# EnvMonitor.net
KiCad netlist of a schematic drawn in Altium Designer
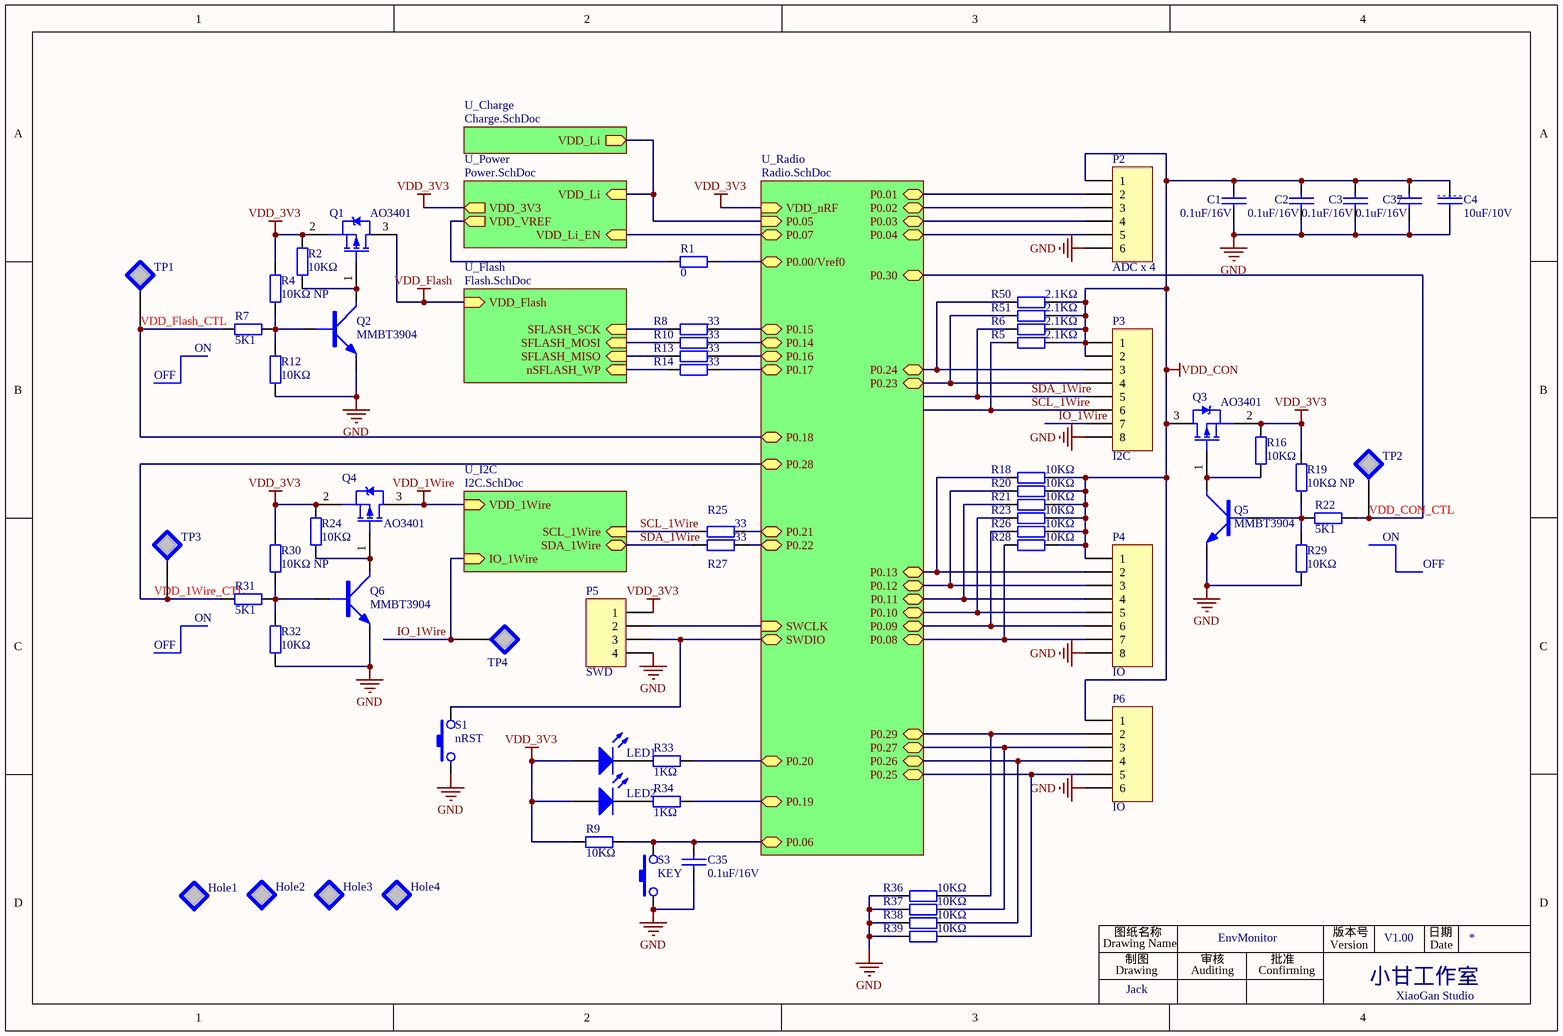
[diagram p0: EnvMonitor.SchDoc]

(export (version "E")
  (design (tool "Eeschema 10.0.6"))
  (components
    (comp (ref "C1")
      (value "0.1uF/16V")
      (footprint "0603R")
      (description "贴片陶瓷电容")
      (libsource (lib "") (part "CAP_1"))
    )
    (comp (ref "C2")
      (value "0.1uF/16V")
      (footprint "0603R")
      (description "贴片陶瓷电容")
      (libsource (lib "") (part "CAP_1"))
    )
    (comp (ref "C3")
      (value "0.1uF/16V")
      (footprint "0603R")
      (description "贴片陶瓷电容")
      (libsource (lib "") (part "CAP_1"))
    )
    (comp (ref "C4")
      (value "10uF/10V")
      (footprint "0805R")
      (description "贴片陶瓷电容")
      (fields (field (name "AUTHOR") "叶建峰"))
      (libsource (lib "*") (part "CAP"))
    )
    (comp (ref "C35")
      (value "0.1uF/16V")
      (footprint "0603R")
      (description "贴片陶瓷电容")
      (libsource (lib "") (part "CAP_1"))
    )
    (comp (ref "C37")
      (value "0.1uF/16V")
      (footprint "0603R")
      (description "贴片陶瓷电容")
      (libsource (lib "") (part "CAP_1"))
    )
    (comp (ref "Hole1")
      (value "~")
      (footprint "HOLE-3.2")
      (description "Test Point")
      (fields (field (name "AUTHOR") "叶建峰"))
      (libsource (lib "") (part "TESTPOINT_1"))
    )
    (comp (ref "Hole2")
      (value "~")
      (footprint "HOLE-3.2")
      (description "Test Point")
      (fields (field (name "AUTHOR") "叶建峰"))
      (libsource (lib "") (part "TESTPOINT_1"))
    )
    (comp (ref "Hole3")
      (value "~")
      (footprint "HOLE-3.2")
      (description "Test Point")
      (fields (field (name "AUTHOR") "叶建峰"))
      (libsource (lib "") (part "TESTPOINT_1"))
    )
    (comp (ref "Hole4")
      (value "~")
      (footprint "HOLE-3.2")
      (description "Test Point")
      (fields (field (name "AUTHOR") "叶建峰"))
      (libsource (lib "") (part "TESTPOINT_1"))
    )
    (comp (ref "LED1")
      (value "LED_0603")
      (footprint "LED-0603")
      (description "LED_0603 Typical RED, GREEN, YELLOW, AMBER GaAs LED")
      (libsource (lib "altium-import") (part "root_0_LED_0603_"))
    )
    (comp (ref "LED2")
      (value "LED_0603")
      (footprint "LED-0603")
      (description "LED_0603 Typical RED, GREEN, YELLOW, AMBER GaAs LED")
      (libsource (lib "altium-import") (part "root_0_LED_0603_"))
    )
    (comp (ref "P2")
      (value "ADC x 4")
      (footprint "CON6-2.0")
      (description "Header, 6-Pin")
      (fields (field (name "PUBLISHER") "Altium Limited"))
      (libsource (lib "Miscellaneous Connectors") (part "Header 6"))
    )
    (comp (ref "P3")
      (value "I2C")
      (footprint "CON8-2.0")
      (description "Header, 8-Pin")
      (fields (field (name "PUBLISHER") "Altium Limited"))
      (libsource (lib "Miscellaneous Connectors") (part "Header 8"))
    )
    (comp (ref "P4")
      (value "IO")
      (footprint "CON8-2.0")
      (description "Header, 8-Pin")
      (fields (field (name "PUBLISHER") "Altium Limited"))
      (libsource (lib "Miscellaneous Connectors") (part "Header 8"))
    )
    (comp (ref "P5")
      (value "SWD")
      (footprint "CON4-2.0")
      (description "Header, 4-Pin")
      (fields (field (name "PUBLISHER") "Altium Limited"))
      (libsource (lib "Miscellaneous Connectors") (part "Header 4"))
    )
    (comp (ref "P6")
      (value "IO")
      (footprint "CON6-2.0")
      (description "Header, 6-Pin")
      (fields (field (name "PUBLISHER") "Altium Limited"))
      (libsource (lib "Miscellaneous Connectors") (part "Header 6"))
    )
    (comp (ref "Q1")
      (value "AO3401")
      (footprint "SOT-23")
      (description "-30V,-3.8A   PMOS  70-120mΩ")
      (fields (field (name "MANUFACTURER") "DIODES"))
      (libsource (lib "led") (part "DMP3098L"))
    )
    (comp (ref "Q2")
      (value "MMBT3904")
      (footprint "SOT-23")
      (description "NPN三极管")
      (libsource (lib "*") (part "9013"))
    )
    (comp (ref "Q3")
      (value "AO3401")
      (footprint "SOT-23")
      (description "-30V,-3.8A   PMOS  70-120mΩ")
      (fields (field (name "MANUFACTURER") "DIODES"))
      (libsource (lib "led") (part "DMP3098L"))
    )
    (comp (ref "Q4")
      (value "AO3401")
      (footprint "SOT-23")
      (description "-30V,-3.8A   PMOS  70-120mΩ")
      (fields (field (name "MANUFACTURER") "DIODES"))
      (libsource (lib "led") (part "DMP3098L"))
    )
    (comp (ref "Q5")
      (value "MMBT3904")
      (footprint "SOT-23")
      (description "NPN三极管")
      (libsource (lib "*") (part "9013"))
    )
    (comp (ref "Q6")
      (value "MMBT3904")
      (footprint "SOT-23")
      (description "NPN三极管")
      (libsource (lib "*") (part "9013"))
    )
    (comp (ref "R1")
      (value "0")
      (footprint "0603R")
      (libsource (lib "altium-import") (part "root_2_RES_0603_"))
    )
    (comp (ref "R2")
      (value "10KΩ")
      (footprint "0603R")
      (libsource (lib "altium-import") (part "root_1_mirrored_RES_0603_"))
    )
    (comp (ref "R4")
      (value "10KΩ NP")
      (footprint "0603R")
      (libsource (lib "altium-import") (part "root_1_mirrored_RES_0603_"))
    )
    (comp (ref "R5")
      (value "2.1KΩ")
      (footprint "0603R")
      (libsource (lib "altium-import") (part "root_2_RES_0603_"))
    )
    (comp (ref "R6")
      (value "2.1KΩ")
      (footprint "0603R")
      (libsource (lib "altium-import") (part "root_2_RES_0603_"))
    )
    (comp (ref "R7")
      (value "5K1")
      (footprint "0603R")
      (libsource (lib "altium-import") (part "root_0_mirrored_RES_0603_"))
    )
    (comp (ref "R8")
      (value "33")
      (footprint "0603R")
      (libsource (lib "altium-import") (part "root_2_RES_0603_"))
    )
    (comp (ref "R9")
      (value "10KΩ")
      (footprint "0603R")
      (libsource (lib "altium-import") (part "root_2_RES_0603_"))
    )
    (comp (ref "R10")
      (value "33")
      (footprint "0603R")
      (libsource (lib "altium-import") (part "root_2_RES_0603_"))
    )
    (comp (ref "R12")
      (value "10KΩ")
      (footprint "0603R")
      (libsource (lib "altium-import") (part "root_1_mirrored_RES_0603_"))
    )
    (comp (ref "R13")
      (value "33")
      (footprint "0603R")
      (libsource (lib "altium-import") (part "root_2_RES_0603_"))
    )
    (comp (ref "R14")
      (value "33")
      (footprint "0603R")
      (libsource (lib "altium-import") (part "root_2_RES_0603_"))
    )
    (comp (ref "R16")
      (value "10KΩ")
      (footprint "0603R")
      (libsource (lib "altium-import") (part "root_1_RES_0603_"))
    )
    (comp (ref "R18")
      (value "10KΩ")
      (footprint "0603R")
      (libsource (lib "altium-import") (part "root_2_RES_0603_"))
    )
    (comp (ref "R19")
      (value "10KΩ NP")
      (footprint "0603R")
      (libsource (lib "altium-import") (part "root_1_RES_0603_"))
    )
    (comp (ref "R20")
      (value "10KΩ")
      (footprint "0603R")
      (libsource (lib "altium-import") (part "root_2_RES_0603_"))
    )
    (comp (ref "R21")
      (value "10KΩ")
      (footprint "0603R")
      (libsource (lib "altium-import") (part "root_2_RES_0603_"))
    )
    (comp (ref "R22")
      (value "5K1")
      (footprint "0603R")
      (libsource (lib "altium-import") (part "root_0_RES_0603_"))
    )
    (comp (ref "R23")
      (value "10KΩ")
      (footprint "0603R")
      (libsource (lib "altium-import") (part "root_2_RES_0603_"))
    )
    (comp (ref "R24")
      (value "10KΩ")
      (footprint "0603R")
      (libsource (lib "altium-import") (part "root_1_mirrored_RES_0603_"))
    )
    (comp (ref "R25")
      (value "33")
      (footprint "0603R")
      (libsource (lib "altium-import") (part "root_2_RES_0603_"))
    )
    (comp (ref "R26")
      (value "10KΩ")
      (footprint "0603R")
      (libsource (lib "altium-import") (part "root_2_RES_0603_"))
    )
    (comp (ref "R27")
      (value "33")
      (footprint "0603R")
      (libsource (lib "altium-import") (part "root_2_RES_0603_"))
    )
    (comp (ref "R28")
      (value "10KΩ")
      (footprint "0603R")
      (libsource (lib "altium-import") (part "root_2_RES_0603_"))
    )
    (comp (ref "R29")
      (value "10KΩ")
      (footprint "0603R")
      (libsource (lib "altium-import") (part "root_1_RES_0603_"))
    )
    (comp (ref "R30")
      (value "10KΩ NP")
      (footprint "0603R")
      (libsource (lib "altium-import") (part "root_1_mirrored_RES_0603_"))
    )
    (comp (ref "R31")
      (value "5K1")
      (footprint "0603R")
      (libsource (lib "altium-import") (part "root_0_mirrored_RES_0603_"))
    )
    (comp (ref "R32")
      (value "10KΩ")
      (footprint "0603R")
      (libsource (lib "altium-import") (part "root_1_mirrored_RES_0603_"))
    )
    (comp (ref "R33")
      (value "1KΩ")
      (footprint "0603R")
      (libsource (lib "altium-import") (part "root_2_RES_0603_"))
    )
    (comp (ref "R34")
      (value "1KΩ")
      (footprint "0603R")
      (libsource (lib "altium-import") (part "root_2_RES_0603_"))
    )
    (comp (ref "R36")
      (value "10KΩ")
      (footprint "0603R")
      (libsource (lib "altium-import") (part "root_2_RES_0603_"))
    )
    (comp (ref "R37")
      (value "10KΩ")
      (footprint "0603R")
      (libsource (lib "altium-import") (part "root_2_RES_0603_"))
    )
    (comp (ref "R38")
      (value "10KΩ")
      (footprint "0603R")
      (libsource (lib "altium-import") (part "root_2_RES_0603_"))
    )
    (comp (ref "R39")
      (value "10KΩ")
      (footprint "0603R")
      (libsource (lib "altium-import") (part "root_2_RES_0603_"))
    )
    (comp (ref "R50")
      (value "2.1KΩ")
      (footprint "0603R")
      (libsource (lib "altium-import") (part "root_2_mirrored_RES_0603_"))
    )
    (comp (ref "R51")
      (value "2.1KΩ")
      (footprint "0603R")
      (libsource (lib "altium-import") (part "root_2_mirrored_RES_0603_"))
    )
    (comp (ref "S1") (value "nRST") (footprint "KEY-6S") (libsource (lib "RC-sheet") (part "SW-PB")))
    (comp (ref "S3") (value "KEY") (footprint "KEY-6S") (libsource (lib "RC-sheet") (part "SW-PB")))
    (comp (ref "TP1")
      (value "~")
      (footprint "MARKER-C")
      (description "Test Point")
      (fields (field (name "AUTHOR") "叶建峰"))
      (libsource (lib "*") (part "TESTPOINT"))
    )
    (comp (ref "TP2")
      (value "~")
      (footprint "MARKER-C")
      (description "Test Point")
      (fields (field (name "AUTHOR") "叶建峰"))
      (libsource (lib "*") (part "TESTPOINT"))
    )
    (comp (ref "TP3")
      (value "~")
      (footprint "MARKER-C")
      (description "Test Point")
      (fields (field (name "AUTHOR") "叶建峰"))
      (libsource (lib "*") (part "TESTPOINT"))
    )
    (comp (ref "TP4")
      (value "~")
      (footprint "MARKER-C")
      (description "Test Point")
      (fields (field (name "AUTHOR") "叶建峰"))
      (libsource (lib "*") (part "TESTPOINT"))
    )
  )
  (nets
    (net (code "1") (name "/IO_1Wire") (class "Default")
      (node (ref "P3") (pin "7") (pinfunction "7_7") (pintype "passive"))
      (node (ref "TP4") (pin "0") (pintype "passive"))
    )
    (net (code "2") (name "/P0.00{slash}Vref0") (class "Default")
      (node (ref "R1") (pin "1") (pinfunction "1_1") (pintype "passive"))
    )
    (net (code "3") (name "/P0.01") (class "Default")
      (node (ref "P2") (pin "2") (pinfunction "2_2") (pintype "passive"))
    )
    (net (code "4") (name "/P0.02") (class "Default")
      (node (ref "P2") (pin "3") (pinfunction "3_3") (pintype "passive"))
    )
    (net (code "5") (name "/P0.03") (class "Default")
      (node (ref "P2") (pin "4") (pinfunction "4_4") (pintype "passive"))
    )
    (net (code "6") (name "/P0.04") (class "Default")
      (node (ref "P2") (pin "5") (pinfunction "5_5") (pintype "passive"))
    )
    (net (code "7") (name "/P0.06") (class "Default")
      (node (ref "C35") (pin "2") (pinfunction "2_2") (pintype "passive"))
      (node (ref "R9") (pin "1") (pinfunction "1_1") (pintype "passive"))
      (node (ref "S3") (pin "2") (pinfunction "2_2") (pintype "passive"))
    )
    (net (code "9") (name "/P0.08") (class "Default")
      (node (ref "P4") (pin "7") (pinfunction "7_7") (pintype "passive"))
      (node (ref "R28") (pin "2") (pinfunction "2_2") (pintype "passive"))
    )
    (net (code "10") (name "/P0.09") (class "Default")
      (node (ref "P4") (pin "6") (pinfunction "6_6") (pintype "passive"))
      (node (ref "R26") (pin "2") (pinfunction "2_2") (pintype "passive"))
    )
    (net (code "11") (name "/P0.10") (class "Default")
      (node (ref "P4") (pin "5") (pinfunction "5_5") (pintype "passive"))
      (node (ref "R23") (pin "2") (pinfunction "2_2") (pintype "passive"))
    )
    (net (code "12") (name "/P0.11") (class "Default")
      (node (ref "P4") (pin "4") (pinfunction "4_4") (pintype "passive"))
      (node (ref "R21") (pin "2") (pinfunction "2_2") (pintype "passive"))
    )
    (net (code "13") (name "/P0.12") (class "Default")
      (node (ref "P4") (pin "3") (pinfunction "3_3") (pintype "passive"))
      (node (ref "R20") (pin "2") (pinfunction "2_2") (pintype "passive"))
    )
    (net (code "14") (name "/P0.13") (class "Default")
      (node (ref "P4") (pin "2") (pinfunction "2_2") (pintype "passive"))
      (node (ref "R18") (pin "2") (pinfunction "2_2") (pintype "passive"))
    )
    (net (code "15") (name "/P0.14") (class "Default")
      (node (ref "R10") (pin "1") (pinfunction "1_1") (pintype "passive"))
    )
    (net (code "16") (name "/P0.15") (class "Default")
      (node (ref "R8") (pin "1") (pinfunction "1_1") (pintype "passive"))
    )
    (net (code "17") (name "/P0.16") (class "Default")
      (node (ref "R13") (pin "1") (pinfunction "1_1") (pintype "passive"))
    )
    (net (code "18") (name "/P0.17") (class "Default")
      (node (ref "R14") (pin "1") (pinfunction "1_1") (pintype "passive"))
    )
    (net (code "19") (name "/P0.19") (class "Default")
      (node (ref "R34") (pin "1") (pinfunction "1_1") (pintype "passive"))
    )
    (net (code "20") (name "/P0.20") (class "Default")
      (node (ref "R33") (pin "1") (pinfunction "1_1") (pintype "passive"))
    )
    (net (code "21") (name "/P0.21") (class "Default")
      (node (ref "R25") (pin "1") (pinfunction "1_1") (pintype "passive"))
    )
    (net (code "22") (name "/P0.22") (class "Default")
      (node (ref "R27") (pin "1") (pinfunction "1_1") (pintype "passive"))
    )
    (net (code "23") (name "/P0.23") (class "Default")
      (node (ref "P3") (pin "4") (pinfunction "4_4") (pintype "passive"))
      (node (ref "R51") (pin "1") (pinfunction "1_1") (pintype "passive"))
    )
    (net (code "24") (name "/P0.24") (class "Default")
      (node (ref "P3") (pin "3") (pinfunction "3_3") (pintype "passive"))
      (node (ref "R50") (pin "1") (pinfunction "1_1") (pintype "passive"))
    )
    (net (code "25") (name "/P0.25") (class "Default")
      (node (ref "P6") (pin "5") (pinfunction "5_5") (pintype "passive"))
      (node (ref "R39") (pin "1") (pinfunction "1_1") (pintype "passive"))
    )
    (net (code "26") (name "/P0.26") (class "Default")
      (node (ref "P6") (pin "4") (pinfunction "4_4") (pintype "passive"))
      (node (ref "R38") (pin "1") (pinfunction "1_1") (pintype "passive"))
    )
    (net (code "27") (name "/P0.27") (class "Default")
      (node (ref "P6") (pin "3") (pinfunction "3_3") (pintype "passive"))
      (node (ref "R37") (pin "1") (pinfunction "1_1") (pintype "passive"))
    )
    (net (code "28") (name "/P0.29") (class "Default")
      (node (ref "P6") (pin "2") (pinfunction "2_2") (pintype "passive"))
      (node (ref "R36") (pin "1") (pinfunction "1_1") (pintype "passive"))
    )
    (net (code "29") (name "/SCL_1Wire") (class "Default")
      (node (ref "P3") (pin "6") (pinfunction "6_6") (pintype "passive"))
      (node (ref "R25") (pin "2") (pinfunction "2_2") (pintype "passive"))
      (node (ref "R5") (pin "2") (pinfunction "2_2") (pintype "passive"))
    )
    (net (code "30") (name "/SDA_1Wire") (class "Default")
      (node (ref "P3") (pin "5") (pinfunction "5_5") (pintype "passive"))
      (node (ref "R27") (pin "2") (pinfunction "2_2") (pintype "passive"))
      (node (ref "R6") (pin "2") (pinfunction "2_2") (pintype "passive"))
    )
    (net (code "31") (name "/SFLASH_MISO") (class "Default")
      (node (ref "R13") (pin "2") (pinfunction "2_2") (pintype "passive"))
    )
    (net (code "32") (name "/SFLASH_MOSI") (class "Default")
      (node (ref "R10") (pin "2") (pinfunction "2_2") (pintype "passive"))
    )
    (net (code "33") (name "/SFLASH_SCK") (class "Default")
      (node (ref "R8") (pin "2") (pinfunction "2_2") (pintype "passive"))
    )
    (net (code "34") (name "/SWCLK") (class "Default")
      (node (ref "P5") (pin "2") (pinfunction "2_2") (pintype "passive"))
    )
    (net (code "35") (name "/SWDIO") (class "Default")
      (node (ref "P5") (pin "3") (pinfunction "3_3") (pintype "passive"))
      (node (ref "S1") (pin "2") (pinfunction "2_2") (pintype "passive"))
    )
    (net (code "36") (name "/VDD_1Wire_CTL") (class "Default")
      (node (ref "R31") (pin "2") (pinfunction "2_2") (pintype "passive"))
      (node (ref "TP3") (pin "0") (pintype "passive"))
    )
    (net (code "37") (name "/VDD_CON_CTL") (class "Default")
      (node (ref "R22") (pin "2") (pinfunction "2_2") (pintype "passive"))
      (node (ref "TP2") (pin "0") (pintype "passive"))
    )
    (net (code "38") (name "/VDD_Flash_CTL") (class "Default")
      (node (ref "R7") (pin "2") (pinfunction "2_2") (pintype "passive"))
      (node (ref "TP1") (pin "0") (pintype "passive"))
    )
    (net (code "40") (name "/VDD_VREF") (class "Default")
      (node (ref "R1") (pin "2") (pinfunction "2_2") (pintype "passive"))
    )
    (net (code "41") (name "/nSFLASH_WP") (class "Default")
      (node (ref "R14") (pin "2") (pinfunction "2_2") (pintype "passive"))
    )
    (net (code "42") (name "GND") (class "Default")
      (node (ref "C1") (pin "2") (pinfunction "2_2") (pintype "passive"))
      (node (ref "C2") (pin "2") (pinfunction "2_2") (pintype "passive"))
      (node (ref "C3") (pin "2") (pinfunction "2_2") (pintype "passive"))
      (node (ref "C35") (pin "1") (pinfunction "1_1") (pintype "passive"))
      (node (ref "C37") (pin "2") (pinfunction "2_2") (pintype "passive"))
      (node (ref "C4") (pin "2") (pinfunction "2_2") (pintype "passive"))
      (node (ref "P2") (pin "6") (pinfunction "6_6") (pintype "passive"))
      (node (ref "P3") (pin "8") (pinfunction "8_8") (pintype "passive"))
      (node (ref "P4") (pin "8") (pinfunction "8_8") (pintype "passive"))
      (node (ref "P5") (pin "4") (pinfunction "4_4") (pintype "passive"))
      (node (ref "P6") (pin "6") (pinfunction "6_6") (pintype "passive"))
      (node (ref "Q2") (pin "2") (pintype "passive"))
      (node (ref "Q5") (pin "2") (pintype "passive"))
      (node (ref "Q6") (pin "2") (pintype "passive"))
      (node (ref "R12") (pin "1") (pinfunction "1_1") (pintype "passive"))
      (node (ref "R29") (pin "1") (pinfunction "1_1") (pintype "passive"))
      (node (ref "R32") (pin "1") (pinfunction "1_1") (pintype "passive"))
      (node (ref "R36") (pin "2") (pinfunction "2_2") (pintype "passive"))
      (node (ref "R37") (pin "2") (pinfunction "2_2") (pintype "passive"))
      (node (ref "R38") (pin "2") (pinfunction "2_2") (pintype "passive"))
      (node (ref "R39") (pin "2") (pinfunction "2_2") (pintype "passive"))
      (node (ref "S1") (pin "1") (pinfunction "1_1") (pintype "passive"))
      (node (ref "S3") (pin "1") (pinfunction "1_1") (pintype "passive"))
    )
    (net (code "43") (name "Net-(LED1-K)") (class "Default")
      (node (ref "LED1") (pin "2") (pinfunction "K_2") (pintype "passive"))
      (node (ref "R33") (pin "2") (pinfunction "2_2") (pintype "passive"))
    )
    (net (code "44") (name "Net-(LED2-K)") (class "Default")
      (node (ref "LED2") (pin "2") (pinfunction "K_2") (pintype "passive"))
      (node (ref "R34") (pin "2") (pinfunction "2_2") (pintype "passive"))
    )
    (net (code "45") (name "Net-(Q1-G)") (class "Default")
      (node (ref "Q1") (pin "1") (pinfunction "G_1") (pintype "passive"))
      (node (ref "Q2") (pin "3") (pintype "passive"))
      (node (ref "R2") (pin "1") (pinfunction "1_1") (pintype "passive"))
    )
    (net (code "46") (name "Net-(Q2-Pad1)") (class "Default")
      (node (ref "Q2") (pin "1") (pintype "passive"))
      (node (ref "R12") (pin "2") (pinfunction "2_2") (pintype "passive"))
      (node (ref "R4") (pin "1") (pinfunction "1_1") (pintype "passive"))
      (node (ref "R7") (pin "1") (pinfunction "1_1") (pintype "passive"))
    )
    (net (code "47") (name "Net-(Q3-G)") (class "Default")
      (node (ref "Q3") (pin "1") (pinfunction "G_1") (pintype "passive"))
      (node (ref "Q5") (pin "3") (pintype "passive"))
      (node (ref "R16") (pin "1") (pinfunction "1_1") (pintype "passive"))
    )
    (net (code "48") (name "Net-(Q4-G)") (class "Default")
      (node (ref "Q4") (pin "1") (pinfunction "G_1") (pintype "passive"))
      (node (ref "Q6") (pin "3") (pintype "passive"))
      (node (ref "R24") (pin "1") (pinfunction "1_1") (pintype "passive"))
    )
    (net (code "49") (name "Net-(Q5-Pad1)") (class "Default")
      (node (ref "Q5") (pin "1") (pintype "passive"))
      (node (ref "R19") (pin "1") (pinfunction "1_1") (pintype "passive"))
      (node (ref "R22") (pin "1") (pinfunction "1_1") (pintype "passive"))
      (node (ref "R29") (pin "2") (pinfunction "2_2") (pintype "passive"))
    )
    (net (code "50") (name "Net-(Q6-Pad1)") (class "Default")
      (node (ref "Q6") (pin "1") (pintype "passive"))
      (node (ref "R30") (pin "1") (pinfunction "1_1") (pintype "passive"))
      (node (ref "R31") (pin "1") (pinfunction "1_1") (pintype "passive"))
      (node (ref "R32") (pin "2") (pinfunction "2_2") (pintype "passive"))
    )
    (net (code "51") (name "VDD_1Wire") (class "Default")
      (node (ref "Q4") (pin "3") (pinfunction "D_3") (pintype "passive"))
    )
    (net (code "52") (name "VDD_3V3") (class "Default")
      (node (ref "LED1") (pin "1") (pinfunction "A_1") (pintype "passive"))
      (node (ref "LED2") (pin "1") (pinfunction "A_1") (pintype "passive"))
      (node (ref "P5") (pin "1") (pinfunction "1_1") (pintype "passive"))
      (node (ref "Q1") (pin "2") (pinfunction "S_2") (pintype "passive"))
      (node (ref "Q3") (pin "2") (pinfunction "S_2") (pintype "passive"))
      (node (ref "Q4") (pin "2") (pinfunction "S_2") (pintype "passive"))
      (node (ref "R16") (pin "2") (pinfunction "2_2") (pintype "passive"))
      (node (ref "R19") (pin "2") (pinfunction "2_2") (pintype "passive"))
      (node (ref "R2") (pin "2") (pinfunction "2_2") (pintype "passive"))
      (node (ref "R24") (pin "2") (pinfunction "2_2") (pintype "passive"))
      (node (ref "R30") (pin "2") (pinfunction "2_2") (pintype "passive"))
      (node (ref "R4") (pin "2") (pinfunction "2_2") (pintype "passive"))
      (node (ref "R9") (pin "2") (pinfunction "2_2") (pintype "passive"))
    )
    (net (code "53") (name "VDD_CON") (class "Default")
      (node (ref "C1") (pin "1") (pinfunction "1_1") (pintype "passive"))
      (node (ref "C2") (pin "1") (pinfunction "1_1") (pintype "passive"))
      (node (ref "C3") (pin "1") (pinfunction "1_1") (pintype "passive"))
      (node (ref "C37") (pin "1") (pinfunction "1_1") (pintype "passive"))
      (node (ref "C4") (pin "1") (pinfunction "1_1") (pintype "passive"))
      (node (ref "P2") (pin "1") (pinfunction "1_1") (pintype "passive"))
      (node (ref "P3") (pin "1") (pinfunction "1_1") (pintype "passive"))
      (node (ref "P3") (pin "2") (pinfunction "2_2") (pintype "passive"))
      (node (ref "P4") (pin "1") (pinfunction "1_1") (pintype "passive"))
      (node (ref "P6") (pin "1") (pinfunction "1_1") (pintype "passive"))
      (node (ref "Q3") (pin "3") (pinfunction "D_3") (pintype "passive"))
      (node (ref "R18") (pin "1") (pinfunction "1_1") (pintype "passive"))
      (node (ref "R20") (pin "1") (pinfunction "1_1") (pintype "passive"))
      (node (ref "R21") (pin "1") (pinfunction "1_1") (pintype "passive"))
      (node (ref "R23") (pin "1") (pinfunction "1_1") (pintype "passive"))
      (node (ref "R26") (pin "1") (pinfunction "1_1") (pintype "passive"))
      (node (ref "R28") (pin "1") (pinfunction "1_1") (pintype "passive"))
      (node (ref "R5") (pin "1") (pinfunction "1_1") (pintype "passive"))
      (node (ref "R50") (pin "2") (pinfunction "2_2") (pintype "passive"))
      (node (ref "R51") (pin "2") (pinfunction "2_2") (pintype "passive"))
      (node (ref "R6") (pin "1") (pinfunction "1_1") (pintype "passive"))
    )
    (net (code "54") (name "VDD_Flash") (class "Default")
      (node (ref "Q1") (pin "3") (pinfunction "D_3") (pintype "passive"))
    )
    (net (code "55") (name "unconnected-(Hole1-Pad0)") (class "Default")
      (node (ref "Hole1") (pin "0") (pintype "passive"))
    )
    (net (code "56") (name "unconnected-(Hole2-Pad0)") (class "Default")
      (node (ref "Hole2") (pin "0") (pintype "passive"))
    )
    (net (code "57") (name "unconnected-(Hole3-Pad0)") (class "Default")
      (node (ref "Hole3") (pin "0") (pintype "passive"))
    )
    (net (code "58") (name "unconnected-(Hole4-Pad0)") (class "Default")
      (node (ref "Hole4") (pin "0") (pintype "passive"))
    )
  )
)
